# IRReceiver.net
KiCad netlist of a schematic drawn in EAGLE
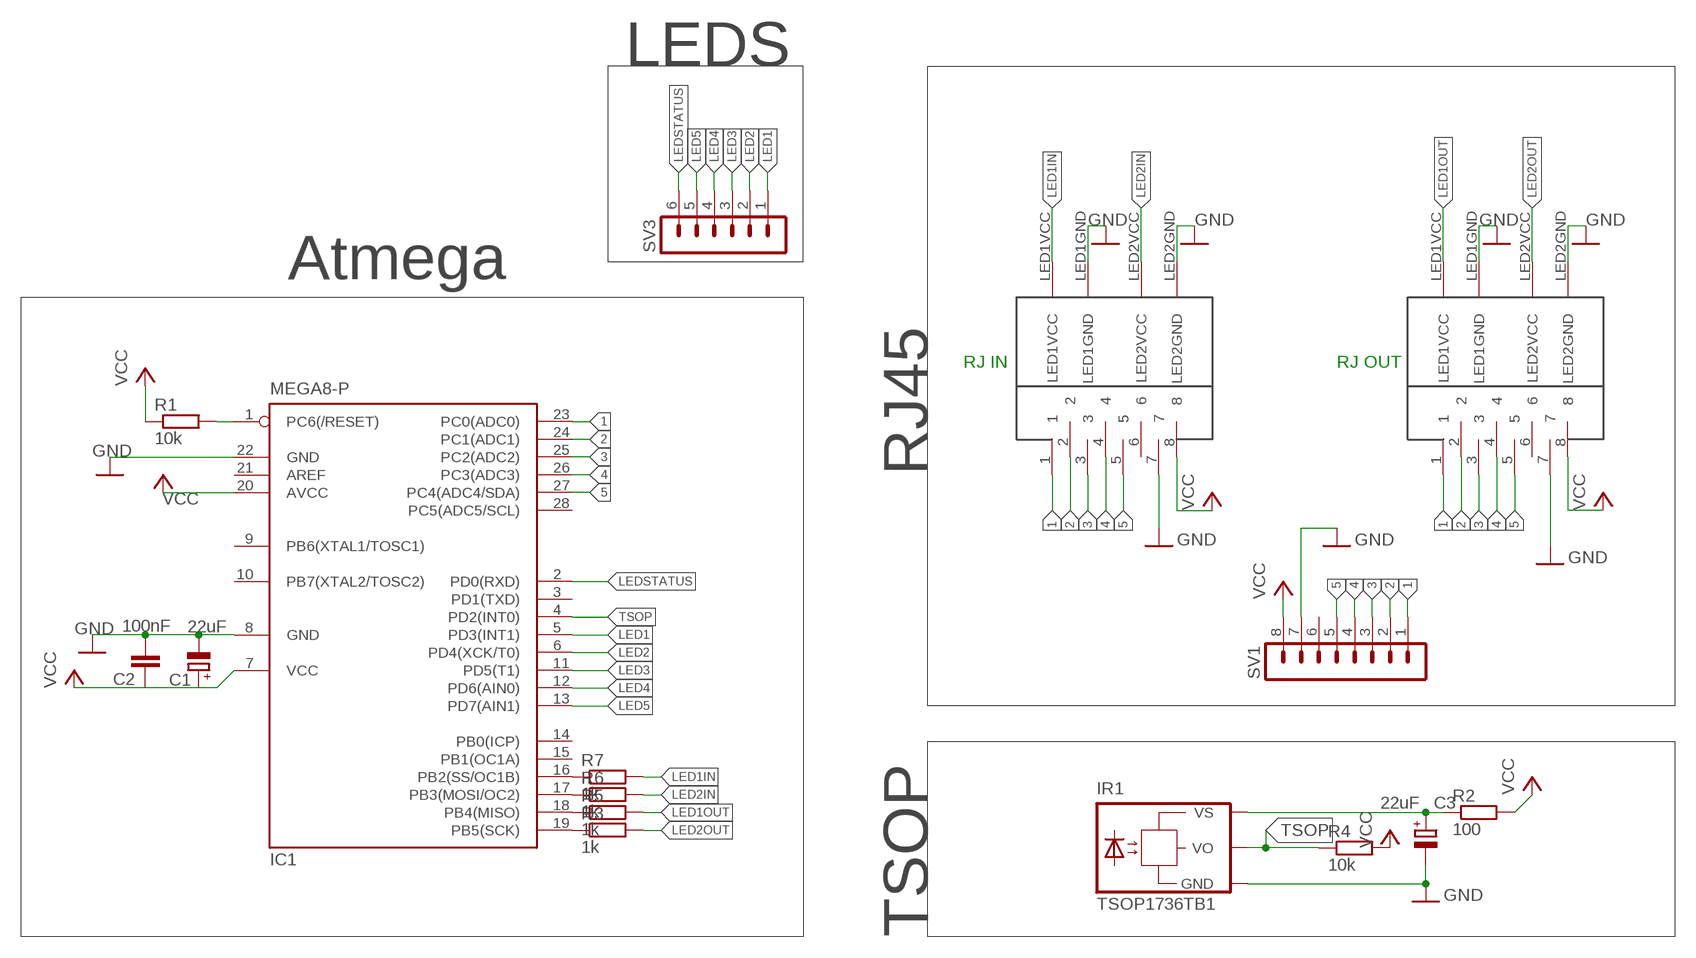
[diagram p0: schematic, sheet 1]

(export (version "E")
  (design (tool "Eeschema 10.0.6"))
  (components
    (comp (ref "C1")
      (value "22uF")
      (footprint "eagle-import:E5-5")
      (libsource (lib "eagle-import") (part "CPOL-EUE5-5"))
    )
    (comp (ref "C2")
      (value "100nF")
      (footprint "eagle-import:C0805")
      (libsource (lib "eagle-import") (part "C-EUC0805"))
    )
    (comp (ref "C3")
      (value "22uF")
      (footprint "eagle-import:E5-5")
      (libsource (lib "eagle-import") (part "CPOL-EUE5-5"))
    )
    (comp (ref "IC1")
      (value "MEGA8-P")
      (footprint "eagle-import:DIL28-3")
      (libsource (lib "eagle-import") (part "MEGA8-P"))
    )
    (comp (ref "IR1")
      (value "TSOP1736TB1")
      (footprint "eagle-import:TSOP17_TB1")
      (libsource (lib "eagle-import") (part "TSOP17TB136"))
    )
    (comp (ref "R1")
      (value "10k")
      (footprint "eagle-import:R0805")
      (libsource (lib "eagle-import") (part "R-EU_R0805"))
    )
    (comp (ref "R2")
      (value "100")
      (footprint "eagle-import:R0805")
      (libsource (lib "eagle-import") (part "R-EU_R0805"))
    )
    (comp (ref "R3")
      (value "1k")
      (footprint "eagle-import:R0805")
      (libsource (lib "eagle-import") (part "R-EU_R0805"))
    )
    (comp (ref "R4")
      (value "10k")
      (footprint "eagle-import:R0805")
      (libsource (lib "eagle-import") (part "R-EU_R0805"))
    )
    (comp (ref "R5")
      (value "1k")
      (footprint "eagle-import:R0805")
      (libsource (lib "eagle-import") (part "R-EU_R0805"))
    )
    (comp (ref "R6")
      (value "1k")
      (footprint "eagle-import:R0805")
      (libsource (lib "eagle-import") (part "R-EU_R0805"))
    )
    (comp (ref "R7")
      (value "1k")
      (footprint "eagle-import:R0805")
      (libsource (lib "eagle-import") (part "R-EU_R0805"))
    )
    (comp (ref "RJIN")
      (value "8P8CLED")
      (footprint "eagle-import:8P8CLED")
      (libsource (lib "eagle-import") (part "8P8CLED"))
    )
    (comp (ref "RJIN1")
      (value "8P8CLED")
      (footprint "eagle-import:8P8CLED")
      (libsource (lib "eagle-import") (part "8P8CLED"))
    )
    (comp (ref "SV1")
      (value "MA08-1")
      (footprint "eagle-import:MA08-1")
      (libsource (lib "eagle-import") (part "MA08-1"))
    )
    (comp (ref "SV3")
      (value "MA06-1")
      (footprint "eagle-import:MA06-1")
      (libsource (lib "eagle-import") (part "MA06-1"))
    )
  )
  (nets
    (net (code "1") (name "1") (class "Default")
      (node (ref "IC1") (pin "23") (pinfunction "PC0(ADC0)_23") (pintype "bidirectional"))
      (node (ref "RJIN") (pin "1") (pinfunction "1_1") (pintype "bidirectional"))
      (node (ref "RJIN1") (pin "1") (pinfunction "1_1") (pintype "bidirectional"))
      (node (ref "SV1") (pin "1") (pinfunction "1_1") (pintype "passive"))
    )
    (net (code "2") (name "2") (class "Default")
      (node (ref "IC1") (pin "24") (pinfunction "PC1(ADC1)_24") (pintype "bidirectional"))
      (node (ref "RJIN") (pin "2") (pinfunction "2_2") (pintype "bidirectional"))
      (node (ref "RJIN1") (pin "2") (pinfunction "2_2") (pintype "bidirectional"))
      (node (ref "SV1") (pin "2") (pinfunction "2_2") (pintype "passive"))
    )
    (net (code "3") (name "3") (class "Default")
      (node (ref "IC1") (pin "25") (pinfunction "PC2(ADC2)_25") (pintype "bidirectional"))
      (node (ref "RJIN") (pin "3") (pinfunction "3_3") (pintype "bidirectional"))
      (node (ref "RJIN1") (pin "3") (pinfunction "3_3") (pintype "bidirectional"))
      (node (ref "SV1") (pin "3") (pinfunction "3_3") (pintype "passive"))
    )
    (net (code "4") (name "4") (class "Default")
      (node (ref "IC1") (pin "26") (pinfunction "PC3(ADC3)_26") (pintype "bidirectional"))
      (node (ref "RJIN") (pin "4") (pinfunction "4_4") (pintype "bidirectional"))
      (node (ref "RJIN1") (pin "4") (pinfunction "4_4") (pintype "bidirectional"))
      (node (ref "SV1") (pin "4") (pinfunction "4_4") (pintype "passive"))
    )
    (net (code "5") (name "5") (class "Default")
      (node (ref "IC1") (pin "27") (pinfunction "PC4(ADC4/SDA)_27") (pintype "bidirectional"))
      (node (ref "RJIN") (pin "5") (pinfunction "5_5") (pintype "bidirectional"))
      (node (ref "RJIN1") (pin "5") (pinfunction "5_5") (pintype "bidirectional"))
      (node (ref "SV1") (pin "5") (pinfunction "5_5") (pintype "passive"))
    )
    (net (code "6") (name "GND") (class "Default")
      (node (ref "C1") (pin "-") (pinfunction "-_-") (pintype "passive"))
      (node (ref "C2") (pin "2") (pinfunction "2_2") (pintype "passive"))
      (node (ref "C3") (pin "-") (pinfunction "-_-") (pintype "passive"))
      (node (ref "IC1") (pin "22") (pinfunction "GND_22") (pintype "power_in"))
      (node (ref "IC1") (pin "8") (pinfunction "GND_8") (pintype "power_in"))
      (node (ref "IR1") (pin "GND") (pinfunction "GND_GND") (pintype "power_in"))
      (node (ref "RJIN") (pin "7") (pinfunction "7_7") (pintype "bidirectional"))
      (node (ref "RJIN") (pin "LED1GND") (pinfunction "LED1GND_LED1GND") (pintype "power_in"))
      (node (ref "RJIN") (pin "LED2GND") (pinfunction "LED2GND_LED2GND") (pintype "power_in"))
      (node (ref "RJIN1") (pin "7") (pinfunction "7_7") (pintype "bidirectional"))
      (node (ref "RJIN1") (pin "LED1GND") (pinfunction "LED1GND_LED1GND") (pintype "power_in"))
      (node (ref "RJIN1") (pin "LED2GND") (pinfunction "LED2GND_LED2GND") (pintype "power_in"))
      (node (ref "SV1") (pin "7") (pinfunction "7_7") (pintype "passive"))
    )
    (net (code "7") (name "LED1") (class "Default")
      (node (ref "IC1") (pin "5") (pinfunction "PD3(INT1)_5") (pintype "bidirectional"))
      (node (ref "SV3") (pin "1") (pinfunction "1_1") (pintype "passive"))
    )
    (net (code "8") (name "LED1IN") (class "Default")
      (node (ref "R7") (pin "2") (pinfunction "2_2") (pintype "passive"))
      (node (ref "RJIN") (pin "LED1VCC") (pinfunction "LED1VCC_LED1VCC") (pintype "power_in"))
    )
    (net (code "9") (name "LED1OUT") (class "Default")
      (node (ref "R5") (pin "2") (pinfunction "2_2") (pintype "passive"))
      (node (ref "RJIN1") (pin "LED1VCC") (pinfunction "LED1VCC_LED1VCC") (pintype "power_in"))
    )
    (net (code "10") (name "LED2") (class "Default")
      (node (ref "IC1") (pin "6") (pinfunction "PD4(XCK/T0)_6") (pintype "bidirectional"))
      (node (ref "SV3") (pin "2") (pinfunction "2_2") (pintype "passive"))
    )
    (net (code "11") (name "LED2IN") (class "Default")
      (node (ref "R6") (pin "2") (pinfunction "2_2") (pintype "passive"))
      (node (ref "RJIN") (pin "LED2VCC") (pinfunction "LED2VCC_LED2VCC") (pintype "power_in"))
    )
    (net (code "12") (name "LED2OUT") (class "Default")
      (node (ref "R3") (pin "2") (pinfunction "2_2") (pintype "passive"))
      (node (ref "RJIN1") (pin "LED2VCC") (pinfunction "LED2VCC_LED2VCC") (pintype "power_in"))
    )
    (net (code "13") (name "LED3") (class "Default")
      (node (ref "IC1") (pin "11") (pinfunction "PD5(T1)_11") (pintype "bidirectional"))
      (node (ref "SV3") (pin "3") (pinfunction "3_3") (pintype "passive"))
    )
    (net (code "14") (name "LED4") (class "Default")
      (node (ref "IC1") (pin "12") (pinfunction "PD6(AIN0)_12") (pintype "bidirectional"))
      (node (ref "SV3") (pin "4") (pinfunction "4_4") (pintype "passive"))
    )
    (net (code "15") (name "LED5") (class "Default")
      (node (ref "IC1") (pin "13") (pinfunction "PD7(AIN1)_13") (pintype "bidirectional"))
      (node (ref "SV3") (pin "5") (pinfunction "5_5") (pintype "passive"))
    )
    (net (code "16") (name "LEDSTATUS") (class "Default")
      (node (ref "IC1") (pin "2") (pinfunction "PD0(RXD)_2") (pintype "bidirectional"))
      (node (ref "SV3") (pin "6") (pinfunction "6_6") (pintype "passive"))
    )
    (net (code "17") (name "Net-(C3-Pad+)") (class "Default")
      (node (ref "C3") (pin "+") (pinfunction "+_+") (pintype "passive"))
      (node (ref "IR1") (pin "VS") (pinfunction "VS_VS") (pintype "power_in"))
      (node (ref "R2") (pin "1") (pinfunction "1_1") (pintype "passive"))
    )
    (net (code "18") (name "Net-(IC1-PB2(SS{slash}OC1B))") (class "Default")
      (node (ref "IC1") (pin "16") (pinfunction "PB2(SS/OC1B)_16") (pintype "bidirectional"))
      (node (ref "R7") (pin "1") (pinfunction "1_1") (pintype "passive"))
    )
    (net (code "19") (name "Net-(IC1-PB3(MOSI{slash}OC2))") (class "Default")
      (node (ref "IC1") (pin "17") (pinfunction "PB3(MOSI/OC2)_17") (pintype "bidirectional"))
      (node (ref "R6") (pin "1") (pinfunction "1_1") (pintype "passive"))
    )
    (net (code "20") (name "Net-(IC1-PB4(MISO))") (class "Default")
      (node (ref "IC1") (pin "18") (pinfunction "PB4(MISO)_18") (pintype "bidirectional"))
      (node (ref "R5") (pin "1") (pinfunction "1_1") (pintype "passive"))
    )
    (net (code "21") (name "Net-(IC1-PB5(SCK))") (class "Default")
      (node (ref "IC1") (pin "19") (pinfunction "PB5(SCK)_19") (pintype "bidirectional"))
      (node (ref "R3") (pin "1") (pinfunction "1_1") (pintype "passive"))
    )
    (net (code "22") (name "Net-(IC1-PC6({slash}RESET))") (class "Default")
      (node (ref "IC1") (pin "1") (pinfunction "PC6(/RESET)_1") (pintype "bidirectional"))
      (node (ref "R1") (pin "2") (pinfunction "2_2") (pintype "passive"))
    )
    (net (code "23") (name "TSOP") (class "Default")
      (node (ref "IC1") (pin "4") (pinfunction "PD2(INT0)_4") (pintype "bidirectional"))
      (node (ref "IR1") (pin "VO") (pinfunction "VO_VO") (pintype "open_collector"))
      (node (ref "R4") (pin "1") (pinfunction "1_1") (pintype "passive"))
    )
    (net (code "24") (name "VCC") (class "Default")
      (node (ref "C1") (pin "+") (pinfunction "+_+") (pintype "passive"))
      (node (ref "C2") (pin "1") (pinfunction "1_1") (pintype "passive"))
      (node (ref "IC1") (pin "20") (pinfunction "AVCC_20") (pintype "power_in"))
      (node (ref "IC1") (pin "7") (pinfunction "VCC_7") (pintype "power_in"))
      (node (ref "R1") (pin "1") (pinfunction "1_1") (pintype "passive"))
      (node (ref "R2") (pin "2") (pinfunction "2_2") (pintype "passive"))
      (node (ref "R4") (pin "2") (pinfunction "2_2") (pintype "passive"))
      (node (ref "RJIN") (pin "8") (pinfunction "8_8") (pintype "bidirectional"))
      (node (ref "RJIN1") (pin "8") (pinfunction "8_8") (pintype "bidirectional"))
      (node (ref "SV1") (pin "8") (pinfunction "8_8") (pintype "passive"))
    )
    (net (code "25") (name "unconnected-(IC1-AREF-Pad21)") (class "Default")
      (node (ref "IC1") (pin "21") (pinfunction "AREF_21") (pintype "passive"))
    )
    (net (code "26") (name "unconnected-(IC1-PB0(ICP)-Pad14)") (class "Default")
      (node (ref "IC1") (pin "14") (pinfunction "PB0(ICP)_14") (pintype "bidirectional"))
    )
    (net (code "27") (name "unconnected-(IC1-PB1(OC1A)-Pad15)") (class "Default")
      (node (ref "IC1") (pin "15") (pinfunction "PB1(OC1A)_15") (pintype "bidirectional"))
    )
    (net (code "28") (name "unconnected-(IC1-PB6(XTAL1{slash}TOSC1)-Pad9)") (class "Default")
      (node (ref "IC1") (pin "9") (pinfunction "PB6(XTAL1/TOSC1)_9") (pintype "bidirectional"))
    )
    (net (code "29") (name "unconnected-(IC1-PB7(XTAL2{slash}TOSC2)-Pad10)") (class "Default")
      (node (ref "IC1") (pin "10") (pinfunction "PB7(XTAL2/TOSC2)_10") (pintype "bidirectional"))
    )
    (net (code "30") (name "unconnected-(IC1-PC5(ADC5{slash}SCL)-Pad28)") (class "Default")
      (node (ref "IC1") (pin "28") (pinfunction "PC5(ADC5/SCL)_28") (pintype "bidirectional"))
    )
    (net (code "31") (name "unconnected-(IC1-PD1(TXD)-Pad3)") (class "Default")
      (node (ref "IC1") (pin "3") (pinfunction "PD1(TXD)_3") (pintype "bidirectional"))
    )
    (net (code "32") (name "unconnected-(RJIN-Pad6)") (class "Default")
      (node (ref "RJIN") (pin "6") (pinfunction "6_6") (pintype "bidirectional"))
    )
    (net (code "33") (name "unconnected-(RJIN1-Pad6)") (class "Default")
      (node (ref "RJIN1") (pin "6") (pinfunction "6_6") (pintype "bidirectional"))
    )
    (net (code "34") (name "unconnected-(SV1-Pad6)") (class "Default")
      (node (ref "SV1") (pin "6") (pinfunction "6_6") (pintype "passive"))
    )
  )
)
